# NO_Output_Processing.net
KiCad netlist of a schematic drawn in Altium Designer
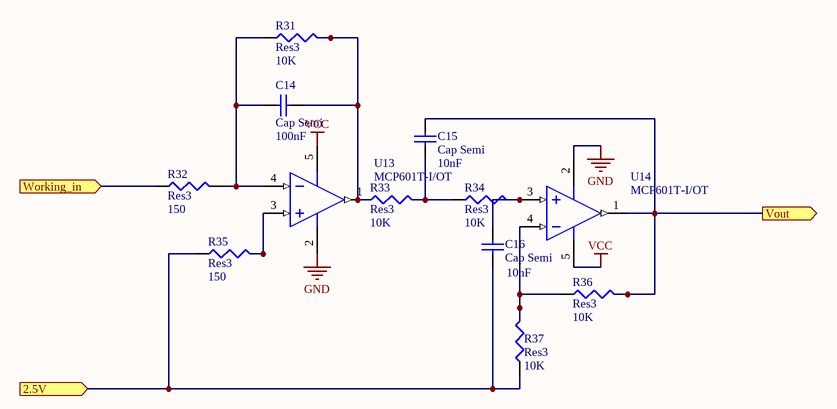
[diagram p0: NO_Output_Processing.SchDoc]

(export (version "E")
  (design (tool "Eeschema 10.0.6"))
  (components
    (comp (ref "C14")
      (value "Cap Semi")
      (footprint "C1206")
      (description "Capacitor (Semiconductor SIM Model)")
      (fields (field (name "ALTIUM_VALUE") "100nF") (field (name "PUBLISHER") "Altium Limited"))
      (libsource (lib "Miscellaneous Devices") (part "Cap Semi"))
    )
    (comp (ref "C15")
      (value "Cap Semi")
      (footprint "C1206")
      (description "Capacitor (Semiconductor SIM Model)")
      (fields (field (name "ALTIUM_VALUE") "10nF") (field (name "PUBLISHER") "Altium Limited"))
      (libsource (lib "Miscellaneous Devices") (part "Cap Semi"))
    )
    (comp (ref "C16")
      (value "Cap Semi")
      (footprint "C1206")
      (description "Capacitor (Semiconductor SIM Model)")
      (fields (field (name "ALTIUM_VALUE") "10nF") (field (name "PUBLISHER") "Altium Limited"))
      (libsource (lib "Miscellaneous Devices") (part "Cap Semi"))
    )
    (comp (ref "R31")
      (value "Res3")
      (footprint "J1-0603")
      (description "Resistor")
      (fields (field (name "ALTIUM_VALUE") "10K") (field (name "PUBLISHER") "Altium Limited"))
      (libsource (lib "Miscellaneous Devices") (part "Res3"))
    )
    (comp (ref "R32")
      (value "Res3")
      (footprint "J1-0603")
      (description "Resistor")
      (fields (field (name "ALTIUM_VALUE") "150") (field (name "PUBLISHER") "Altium Limited"))
      (libsource (lib "Miscellaneous Devices") (part "Res3"))
    )
    (comp (ref "R33")
      (value "Res3")
      (footprint "J1-0603")
      (description "Resistor")
      (fields (field (name "ALTIUM_VALUE") "10K") (field (name "PUBLISHER") "Altium Limited"))
      (libsource (lib "Miscellaneous Devices") (part "Res3"))
    )
    (comp (ref "R34")
      (value "Res3")
      (footprint "J1-0603")
      (description "Resistor")
      (fields (field (name "ALTIUM_VALUE") "10K") (field (name "PUBLISHER") "Altium Limited"))
      (libsource (lib "Miscellaneous Devices") (part "Res3"))
    )
    (comp (ref "R35")
      (value "Res3")
      (footprint "J1-0603")
      (description "Resistor")
      (fields (field (name "ALTIUM_VALUE") "150") (field (name "PUBLISHER") "Altium Limited"))
      (libsource (lib "Miscellaneous Devices") (part "Res3"))
    )
    (comp (ref "R36")
      (value "Res3")
      (footprint "J1-0603")
      (description "Resistor")
      (fields (field (name "ALTIUM_VALUE") "10K") (field (name "PUBLISHER") "Altium Limited"))
      (libsource (lib "Miscellaneous Devices") (part "Res3"))
    )
    (comp (ref "R37")
      (value "Res3")
      (footprint "J1-0603")
      (description "Resistor")
      (fields (field (name "ALTIUM_VALUE") "10K") (field (name "PUBLISHER") "Altium Limited"))
      (libsource (lib "Miscellaneous Devices") (part "Res3"))
    )
    (comp (ref "U13")
      (value "MCP601T-I/OT")
      (footprint "SOT-23-OT5_L")
      (libsource (lib "Altium Content Vault") (part "AMP-OPA-MCP601-SOT5"))
    )
    (comp (ref "U14")
      (value "MCP601T-I/OT")
      (footprint "SOT-23-OT5_L")
      (libsource (lib "Altium Content Vault") (part "AMP-OPA-MCP601-SOT5"))
    )
  )
  (nets
    (net (code "1") (name "/2.5V") (class "Default")
      (node (ref "C16") (pin "1") (pinfunction "1_1") (pintype "passive"))
      (node (ref "R35") (pin "1") (pinfunction "1_1") (pintype "passive"))
      (node (ref "R37") (pin "1") (pinfunction "1_1") (pintype "passive"))
    )
    (net (code "2") (name "/Vout") (class "Default")
      (node (ref "C15") (pin "2") (pinfunction "2_2") (pintype "passive"))
      (node (ref "R36") (pin "2") (pinfunction "2_2") (pintype "passive"))
      (node (ref "U14") (pin "1") (pinfunction "VOUT_1") (pintype "output"))
    )
    (net (code "3") (name "/Working_in") (class "Default")
      (node (ref "R32") (pin "1") (pinfunction "1_1") (pintype "passive"))
    )
    (net (code "4") (name "GND") (class "Default")
      (node (ref "U13") (pin "2") (pinfunction "VSS_2") (pintype "power_in"))
      (node (ref "U14") (pin "2") (pinfunction "VSS_2") (pintype "power_in"))
    )
    (net (code "5") (name "Net-(C15-Pad1)") (class "Default")
      (node (ref "C15") (pin "1") (pinfunction "1_1") (pintype "passive"))
      (node (ref "R33") (pin "2") (pinfunction "2_2") (pintype "passive"))
      (node (ref "R34") (pin "1") (pinfunction "1_1") (pintype "passive"))
    )
    (net (code "6") (name "Net-(U13-VIN+)") (class "Default")
      (node (ref "R35") (pin "2") (pinfunction "2_2") (pintype "passive"))
      (node (ref "U13") (pin "3") (pinfunction "VIN+_3") (pintype "input"))
    )
    (net (code "7") (name "Net-(U13-VIN-)") (class "Default")
      (node (ref "C14") (pin "1") (pinfunction "1_1") (pintype "passive"))
      (node (ref "R31") (pin "1") (pinfunction "1_1") (pintype "passive"))
      (node (ref "R32") (pin "2") (pinfunction "2_2") (pintype "passive"))
      (node (ref "U13") (pin "4") (pinfunction "VIN-_4") (pintype "input"))
    )
    (net (code "8") (name "Net-(U13-VOUT)") (class "Default")
      (node (ref "C14") (pin "2") (pinfunction "2_2") (pintype "passive"))
      (node (ref "R31") (pin "2") (pinfunction "2_2") (pintype "passive"))
      (node (ref "R33") (pin "1") (pinfunction "1_1") (pintype "passive"))
      (node (ref "U13") (pin "1") (pinfunction "VOUT_1") (pintype "output"))
    )
    (net (code "9") (name "Net-(U14-VIN+)") (class "Default")
      (node (ref "C16") (pin "2") (pinfunction "2_2") (pintype "passive"))
      (node (ref "R34") (pin "2") (pinfunction "2_2") (pintype "passive"))
      (node (ref "U14") (pin "3") (pinfunction "VIN+_3") (pintype "input"))
    )
    (net (code "10") (name "Net-(U14-VIN-)") (class "Default")
      (node (ref "R36") (pin "1") (pinfunction "1_1") (pintype "passive"))
      (node (ref "R37") (pin "2") (pinfunction "2_2") (pintype "passive"))
      (node (ref "U14") (pin "4") (pinfunction "VIN-_4") (pintype "input"))
    )
    (net (code "11") (name "VCC") (class "Default")
      (node (ref "U13") (pin "5") (pinfunction "VDD_5") (pintype "power_in"))
      (node (ref "U14") (pin "5") (pinfunction "VDD_5") (pintype "power_in"))
    )
  )
)
